# walktimizer.net
KiCad netlist of a schematic drawn in Altium Designer
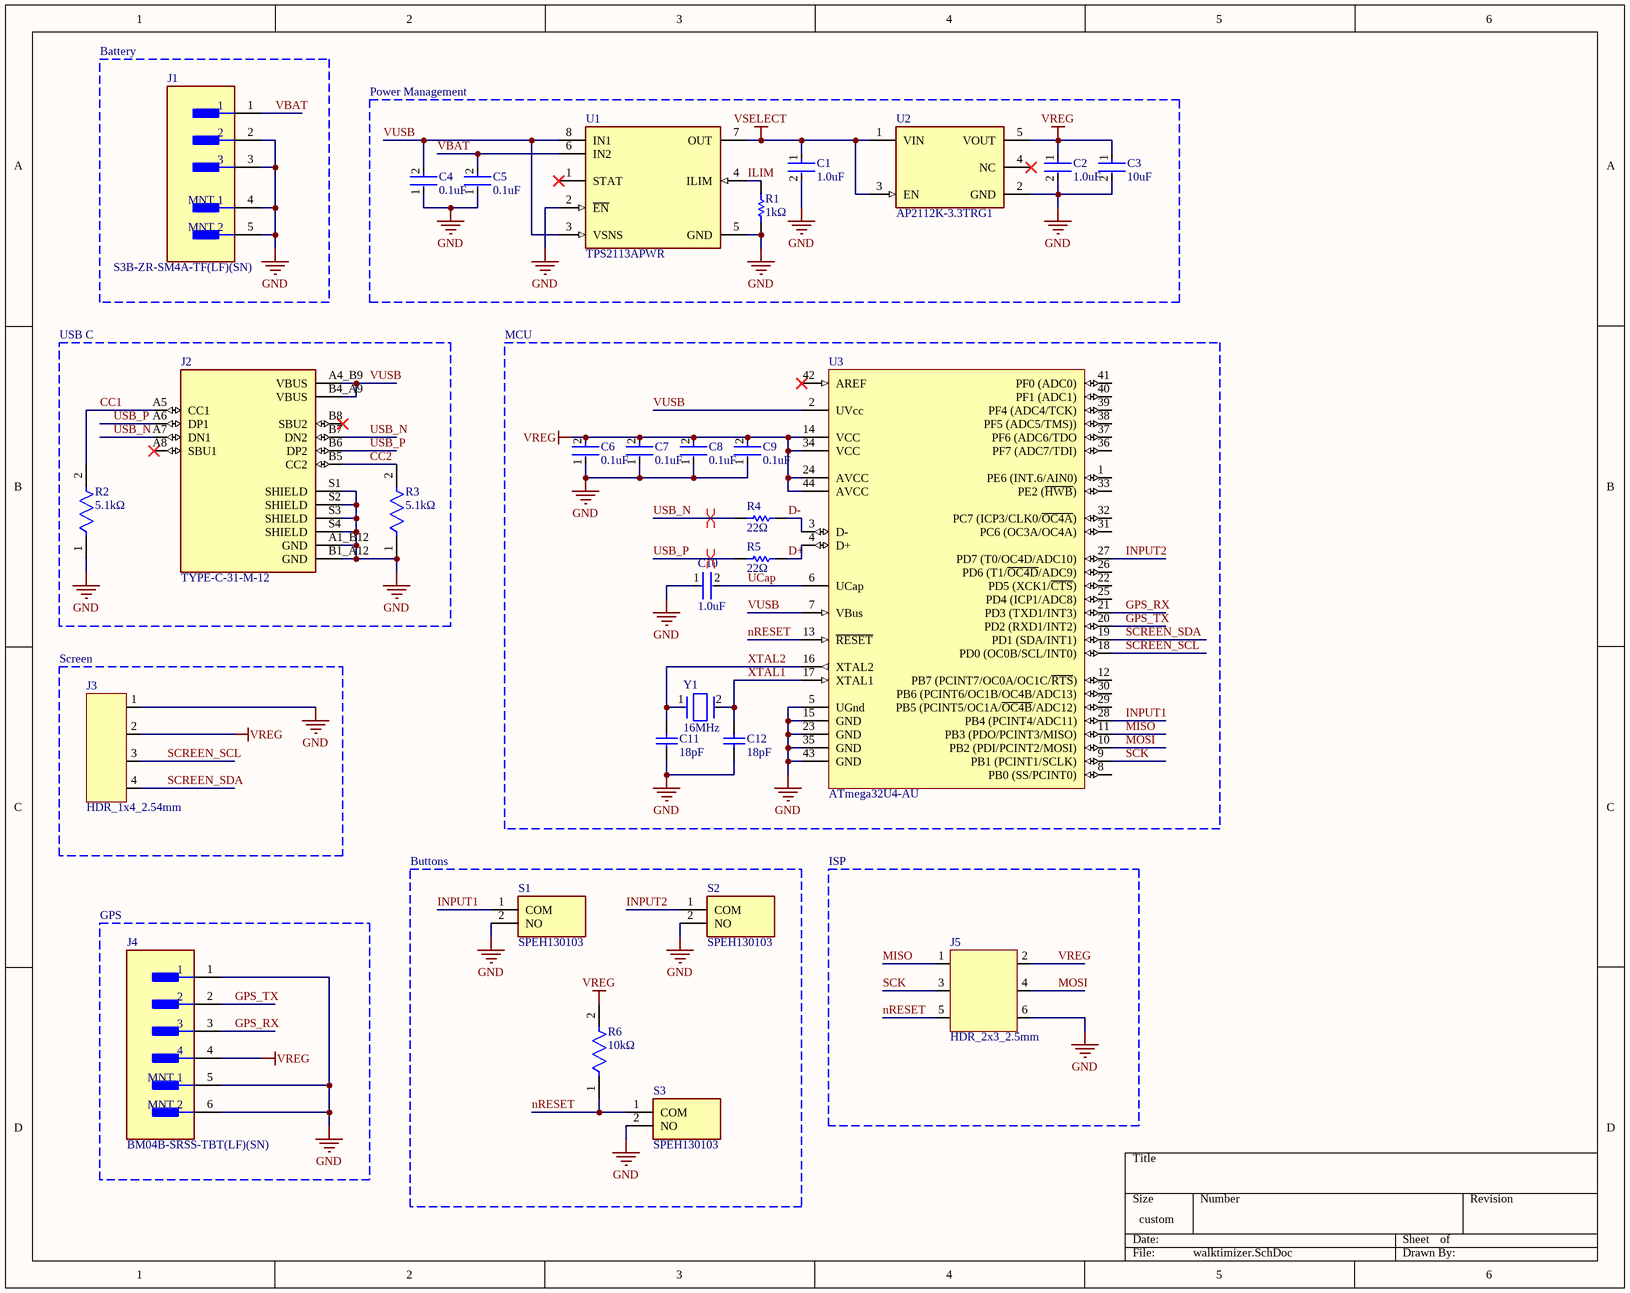
[diagram p0: walktimizer.SchDoc]

(export (version "E")
  (design (tool "Eeschema 10.0.6"))
  (components
    (comp (ref "C1")
      (value "1.0uF")
      (footprint "FP-GRT188-0_1-e0_2_0_5-IPC_B")
      (description "Multi-Layer Ceramic Capacitor 1uF 50V X5R ±10% 0603 Paper T/R\r\nGRT188R61H105KE13D")
      (fields (field (name "TOLERANCE") "10%"))
      (libsource (lib "Altium Content Vault") (part "02cd4be3c70576c341d710602a673aa"))
    )
    (comp (ref "C2")
      (value "1.0uF")
      (footprint "FP-GRT188-0_1-e0_2_0_5-IPC_B")
      (description "Multi-Layer Ceramic Capacitor 1uF 50V X5R ±10% 0603 Paper T/R\r\nGRT188R61H105KE13D")
      (fields (field (name "TOLERANCE") "10%"))
      (libsource (lib "Altium Content Vault") (part "02cd4be3c70576c341d710602a673aa"))
    )
    (comp (ref "C3")
      (value "10uF")
      (footprint "FP-GRM188-0_1-e0_2_0_55-IPC_A")
      (fields (field (name "VOLTAGE") "6.3V") (field (name "TOLERANCE") "20%"))
      (libsource (lib "Altium Content Vault") (part "02cd4be3c70576c341d710602a673aa"))
    )
    (comp (ref "C4")
      (value "0.1uF")
      (footprint "FP-GRM15-MFG")
      (description "CAP CER 0.1UF 16V X7R 0402\r\n\r\nGRM155R71C104KA88D")
      (fields (field (name "MANUFACTURER PART NUMBER") "GRM155R71C104KA88D") (field (name "TOLERANCE") "10%"))
      (libsource (lib "Altium Content Vault") (part "236180d848d6139a670b325ea6854c9"))
    )
    (comp (ref "C5")
      (value "0.1uF")
      (footprint "FP-GRM15-MFG")
      (description "CAP CER 0.1UF 16V X7R 0402\r\n\r\nGRM155R71C104KA88D")
      (fields (field (name "MANUFACTURER PART NUMBER") "GRM155R71C104KA88D") (field (name "TOLERANCE") "10%"))
      (libsource (lib "Altium Content Vault") (part "236180d848d6139a670b325ea6854c9"))
    )
    (comp (ref "C6")
      (value "0.1uF")
      (footprint "FP-GRM15-MFG")
      (description "CAP CER 0.1UF 16V X7R 0402\r\n\r\nGRM155R71C104KA88D")
      (fields (field (name "MANUFACTURER PART NUMBER") "GRM155R71C104KA88D") (field (name "TOLERANCE") "10%"))
      (libsource (lib "Altium Content Vault") (part "236180d848d6139a670b325ea6854c9"))
    )
    (comp (ref "C7")
      (value "0.1uF")
      (footprint "FP-GRM15-MFG")
      (description "CAP CER 0.1UF 16V X7R 0402\r\n\r\nGRM155R71C104KA88D")
      (fields (field (name "MANUFACTURER PART NUMBER") "GRM155R71C104KA88D") (field (name "TOLERANCE") "10%"))
      (libsource (lib "Altium Content Vault") (part "236180d848d6139a670b325ea6854c9"))
    )
    (comp (ref "C8")
      (value "0.1uF")
      (footprint "FP-GRM15-MFG")
      (description "CAP CER 0.1UF 16V X7R 0402\r\n\r\nGRM155R71C104KA88D")
      (fields (field (name "MANUFACTURER PART NUMBER") "GRM155R71C104KA88D") (field (name "TOLERANCE") "10%"))
      (libsource (lib "Altium Content Vault") (part "236180d848d6139a670b325ea6854c9"))
    )
    (comp (ref "C9")
      (value "0.1uF")
      (footprint "FP-GRM15-MFG")
      (description "CAP CER 0.1UF 16V X7R 0402\r\n\r\nGRM155R71C104KA88D")
      (fields (field (name "MANUFACTURER PART NUMBER") "GRM155R71C104KA88D") (field (name "TOLERANCE") "10%"))
      (libsource (lib "Altium Content Vault") (part "236180d848d6139a670b325ea6854c9"))
    )
    (comp (ref "C10")
      (value "1.0uF")
      (footprint "FP-GRT188-0_1-e0_2_0_5-IPC_B")
      (description "Multi-Layer Ceramic Capacitor 1uF 50V X5R ±10% 0603 Paper T/R\r\nGRT188R61H105KE13D")
      (fields (field (name "TOLERANCE") "10%"))
      (libsource (lib "Altium Content Vault") (part "02cd4be3c70576c341d710602a673aa"))
    )
    (comp (ref "C11")
      (value "18pF")
      (footprint "CAPC1608X90X40LL10T20")
      (fields (field (name "TOLERANCE") "1%"))
      (libsource (lib "Altium Content Vault") (part "CAP-NP-2"))
    )
    (comp (ref "C12")
      (value "18pF")
      (footprint "CAPC1608X90X40LL10T20")
      (fields (field (name "TOLERANCE") "1%"))
      (libsource (lib "Altium Content Vault") (part "CAP-NP-2"))
    )
    (comp (ref "J1")
      (value "S3B-ZR-SM4A-TF(LF)(SN)")
      (footprint "FP-S3B-ZR-SM4A-TF_LF_SN-MFG")
      (description "CONN HEADER SMD R/A 3POS 1.5MM")
      (libsource (lib "Altium Content Vault") (part "38689d6f3df0f9b234c6ddcef280d85"))
    )
    (comp (ref "J2")
      (value "TYPE-C-31-M-12")
      (footprint "HRO_TYPE-C-31-M-12")
      (description "USB Connectors 24 Receptacle 1 8.94*7.3mm RoHS")
      (fields (field (name "MF") "HRO Electronics Co., Ltd."))
      (libsource (lib "TYPE-C-31-M-12") (part "TYPE-C-31-M-12"))
    )
    (comp (ref "J3")
      (value "HDR_1x4_2.54mm")
      (footprint "HDR_1x4_2.5mm_TH")
      (description "2x3 2.54mm Pitch Header")
      (libsource (lib "symbolism") (part "HDR_1x4_2.54mm"))
    )
    (comp (ref "J4")
      (value "BM04B-SRSS-TBT(LF)(SN)")
      (footprint "FP-BM04B-SRSS-TBT_LF_SN-MFG")
      (description "CONN HEADER SMD 4POS 1MM")
      (libsource (lib "Altium Content Vault") (part "8e3688c4b118bffc0dd9b7401e414ba"))
    )
    (comp (ref "J5")
      (value "HDR_2x3_2.5mm")
      (footprint "HDR_2x3_2.5mm_TH")
      (description "2x3 2.54mm Pitch Header")
      (libsource (lib "symbolism") (part "HDR_2x3_2.5mm"))
    )
    (comp (ref "R1")
      (value "1kΩ")
      (footprint "RESC2013X60X35ML10T20")
      (fields (field (name "TOLERANCE") "1%") (field (name "MANUFACTURER") "Yageo"))
      (libsource (lib "Altium Content Vault") (part "RES-2"))
    )
    (comp (ref "R2")
      (value "5.1kΩ")
      (footprint "FP-CRCW0603-e3-IPC_C")
      (description "RES Thick Film, 5.1kΩ, 1%, 0.1W, 100ppm/°C, 0603\r\n\r\nCRCW06035K10FKEA")
      (fields (field (name "TOLERANCE") "1%"))
      (libsource (lib "Altium Content Vault") (part "1029c3af85768c4190bb7ad29bc67b5"))
    )
    (comp (ref "R3")
      (value "5.1kΩ")
      (footprint "FP-CRCW0603-e3-IPC_C")
      (description "RES Thick Film, 5.1kΩ, 1%, 0.1W, 100ppm/°C, 0603\r\n\r\nCRCW06035K10FKEA")
      (fields (field (name "TOLERANCE") "1%"))
      (libsource (lib "Altium Content Vault") (part "1029c3af85768c4190bb7ad29bc67b5"))
    )
    (comp (ref "R4")
      (value "22Ω")
      (footprint "RESC1005X40X25LL05T05")
      (description "CRCW040222R0FKED")
      (fields (field (name "MANUFACTURER") "Vishay Dale"))
      (libsource (lib "Altium Content Vault") (part "RES"))
    )
    (comp (ref "R5")
      (value "22Ω")
      (footprint "RESC1005X40X25LL05T05")
      (description "CRCW040222R0FKED")
      (fields (field (name "MANUFACTURER") "Vishay Dale"))
      (libsource (lib "Altium Content Vault") (part "RES"))
    )
    (comp (ref "R6")
      (value "10kΩ")
      (footprint "FP-RC0603-0_55-IPC_C")
      (description "RES 10K OHM 1% 1/10W 0603\r\nRC0603FR-0710KL")
      (fields (field (name "TOLERANCE") "1%"))
      (libsource (lib "Altium Content Vault") (part "1029c3af85768c4190bb7ad29bc67b5"))
    )
    (comp (ref "S1")
      (value "SPEH130103")
      (footprint "SamacSys:SPEH130103")
      (description "Switch")
      (fields (field (name "MOUSER PART NUMBER") "688-SPEH130101"))
      (libsource (lib "*") (part "SPEH130103"))
    )
    (comp (ref "S2")
      (value "SPEH130103")
      (footprint "SamacSys:SPEH130103")
      (description "Switch")
      (fields (field (name "MOUSER PART NUMBER") "688-SPEH130101"))
      (libsource (lib "*") (part "SPEH130103"))
    )
    (comp (ref "S3")
      (value "SPEH130103")
      (footprint "SamacSys:SPEH130103")
      (description "Switch")
      (fields (field (name "MOUSER PART NUMBER") "688-SPEH130101"))
      (libsource (lib "*") (part "SPEH130103"))
    )
    (comp (ref "U1")
      (value "TPS2113APWR")
      (footprint "FP-PW0008A-IPC_B")
      (description "IC OR CTRLR SRC SELECT 8TSSOP")
      (libsource (lib "Altium Content Vault") (part "883c2ec5d874d1801bc805f681b0625"))
    )
    (comp (ref "U2")
      (value "AP2112K-3.3TRG1")
      (footprint "FP-SOT25-IPC_A")
      (description "IC REG LINEAR 3.3V 600MA SOT25")
      (libsource (lib "Altium Content Vault") (part "c8ab751aee5229183125ab046a11caa"))
    )
    (comp (ref "U3")
      (value "ATmega32U4-AU")
      (footprint "44ML_M")
      (libsource (lib "Altium Content Vault") (part "MC-8B-ATM16U4-SQ44"))
    )
    (comp (ref "Y1")
      (value "16MHz")
      (footprint "FP-ABM3-MFG")
      (description "Crystal 16MHz ±20ppm 18pF SMD-2 5mm x 3.2mm\r\n\r\nABM3-16.000MHZ-D2Y-T")
      (fields (field (name "TOLERANCE") "20ppm"))
      (libsource (lib "Altium Content Vault") (part "c23a69dc6c9e2f18f2079038eb95dd1"))
    )
  )
  (nets
    (net (code "1") (name "/CC1") (class "Default")
      (node (ref "J2") (pin "A5") (pinfunction "CC1_A5") (pintype "bidirectional"))
      (node (ref "R2") (pin "2") (pinfunction "2_2") (pintype "passive"))
    )
    (net (code "2") (name "/CC2") (class "Default")
      (node (ref "J2") (pin "B5") (pinfunction "CC2_B5") (pintype "bidirectional"))
      (node (ref "R3") (pin "2") (pinfunction "2_2") (pintype "passive"))
    )
    (net (code "3") (name "/D+") (class "Default")
      (node (ref "R5") (pin "2") (pinfunction "2_2") (pintype "passive"))
      (node (ref "U3") (pin "4") (pinfunction "D+_4") (pintype "bidirectional"))
    )
    (net (code "4") (name "/D-") (class "Default")
      (node (ref "R4") (pin "2") (pinfunction "2_2") (pintype "passive"))
      (node (ref "U3") (pin "3") (pinfunction "D-_3") (pintype "bidirectional"))
    )
    (net (code "5") (name "/GPS_RX") (class "Default")
      (node (ref "J4") (pin "3") (pinfunction "3_3") (pintype "passive"))
      (node (ref "U3") (pin "21") (pinfunction "PD3_(TXD1/INT3)_21") (pintype "bidirectional"))
    )
    (net (code "6") (name "/GPS_TX") (class "Default")
      (node (ref "J4") (pin "2") (pinfunction "2_2") (pintype "passive"))
      (node (ref "U3") (pin "20") (pinfunction "PD2_(RXD1/INT2)_20") (pintype "bidirectional"))
    )
    (net (code "7") (name "/ILIM") (class "Default")
      (node (ref "R1") (pin "2") (pinfunction "2_2") (pintype "passive"))
      (node (ref "U1") (pin "4") (pinfunction "ILIM_4") (pintype "input"))
    )
    (net (code "8") (name "/INPUT1") (class "Default")
      (node (ref "S1") (pin "1") (pinfunction "COM_1") (pintype "passive"))
      (node (ref "U3") (pin "28") (pinfunction "PB4_(PCINT4/ADC11)_28") (pintype "bidirectional"))
    )
    (net (code "9") (name "/INPUT2") (class "Default")
      (node (ref "S2") (pin "1") (pinfunction "COM_1") (pintype "passive"))
      (node (ref "U3") (pin "27") (pinfunction "PD7_(T0/OC4D/ADC10)_27") (pintype "bidirectional"))
    )
    (net (code "10") (name "/MISO") (class "Default")
      (node (ref "J5") (pin "1") (pintype "passive"))
      (node (ref "U3") (pin "11") (pinfunction "PB3_(PDO/PCINT3/MISO)_11") (pintype "bidirectional"))
    )
    (net (code "11") (name "/MOSI") (class "Default")
      (node (ref "J5") (pin "4") (pintype "passive"))
      (node (ref "U3") (pin "10") (pinfunction "PB2_(PDI/PCINT2/MOSI)_10") (pintype "bidirectional"))
    )
    (net (code "12") (name "/SCK") (class "Default")
      (node (ref "J5") (pin "3") (pintype "passive"))
      (node (ref "U3") (pin "9") (pinfunction "PB1_(PCINT1/SCLK)_9") (pintype "bidirectional"))
    )
    (net (code "13") (name "/SCREEN_SCL") (class "Default")
      (node (ref "J3") (pin "3") (pintype "passive"))
      (node (ref "U3") (pin "18") (pinfunction "PD0_(OC0B/SCL/INT0)_18") (pintype "bidirectional"))
    )
    (net (code "14") (name "/SCREEN_SDA") (class "Default")
      (node (ref "J3") (pin "4") (pintype "passive"))
      (node (ref "U3") (pin "19") (pinfunction "PD1_(SDA/INT1)_19") (pintype "bidirectional"))
    )
    (net (code "15") (name "/UCap") (class "Default")
      (node (ref "C10") (pin "2") (pinfunction "2_2") (pintype "passive"))
      (node (ref "U3") (pin "6") (pinfunction "UCap_6") (pintype "passive"))
    )
    (net (code "16") (name "/USB_N") (class "Default")
      (node (ref "J2") (pin "A7") (pinfunction "DN1_A7") (pintype "bidirectional"))
      (node (ref "J2") (pin "B7") (pinfunction "DN2_B7") (pintype "bidirectional"))
      (node (ref "R4") (pin "1") (pinfunction "1_1") (pintype "passive"))
    )
    (net (code "17") (name "/USB_P") (class "Default")
      (node (ref "J2") (pin "A6") (pinfunction "DP1_A6") (pintype "bidirectional"))
      (node (ref "J2") (pin "B6") (pinfunction "DP2_B6") (pintype "bidirectional"))
      (node (ref "R5") (pin "1") (pinfunction "1_1") (pintype "passive"))
    )
    (net (code "18") (name "/VBAT") (class "Default")
      (node (ref "C5") (pin "2") (pinfunction "2_2") (pintype "passive"))
      (node (ref "J1") (pin "1") (pinfunction "1_1") (pintype "passive"))
      (node (ref "U1") (pin "6") (pinfunction "IN2_6") (pintype "power_in"))
    )
    (net (code "19") (name "/VUSB") (class "Default")
      (node (ref "C4") (pin "2") (pinfunction "2_2") (pintype "passive"))
      (node (ref "J2") (pin "A4_B9") (pinfunction "VBUS_A4_B9") (pintype "power_in"))
      (node (ref "J2") (pin "B4_A9") (pinfunction "VBUS_B4_A9") (pintype "power_in"))
      (node (ref "U1") (pin "3") (pinfunction "VSNS_3") (pintype "input"))
      (node (ref "U1") (pin "8") (pinfunction "IN1_8") (pintype "power_in"))
      (node (ref "U3") (pin "2") (pinfunction "UVcc_2") (pintype "power_in"))
      (node (ref "U3") (pin "7") (pinfunction "VBus_7") (pintype "input"))
    )
    (net (code "20") (name "/XTAL1") (class "Default")
      (node (ref "C12") (pin "2") (pinfunction "2_2") (pintype "passive"))
      (node (ref "U3") (pin "17") (pinfunction "XTAL1_17") (pintype "input"))
      (node (ref "Y1") (pin "2") (pinfunction "2_2") (pintype "passive"))
    )
    (net (code "21") (name "/XTAL2") (class "Default")
      (node (ref "C11") (pin "2") (pinfunction "2_2") (pintype "passive"))
      (node (ref "U3") (pin "16") (pinfunction "XTAL2_16") (pintype "output"))
      (node (ref "Y1") (pin "1") (pinfunction "1_1") (pintype "passive"))
    )
    (net (code "22") (name "/nRESET") (class "Default")
      (node (ref "J5") (pin "5") (pintype "passive"))
      (node (ref "R6") (pin "1") (pinfunction "1_1") (pintype "passive"))
      (node (ref "S3") (pin "1") (pinfunction "COM_1") (pintype "passive"))
      (node (ref "U3") (pin "13") (pinfunction "~{RESET}_13") (pintype "input"))
    )
    (net (code "23") (name "GND") (class "Default")
      (node (ref "C1") (pin "2") (pinfunction "2_2") (pintype "passive"))
      (node (ref "C10") (pin "1") (pinfunction "1_1") (pintype "passive"))
      (node (ref "C11") (pin "1") (pinfunction "1_1") (pintype "passive"))
      (node (ref "C12") (pin "1") (pinfunction "1_1") (pintype "passive"))
      (node (ref "C2") (pin "2") (pinfunction "2_2") (pintype "passive"))
      (node (ref "C3") (pin "2") (pinfunction "2_2") (pintype "passive"))
      (node (ref "C4") (pin "1") (pinfunction "1_1") (pintype "passive"))
      (node (ref "C5") (pin "1") (pinfunction "1_1") (pintype "passive"))
      (node (ref "C6") (pin "1") (pinfunction "1_1") (pintype "passive"))
      (node (ref "C7") (pin "1") (pinfunction "1_1") (pintype "passive"))
      (node (ref "C8") (pin "1") (pinfunction "1_1") (pintype "passive"))
      (node (ref "C9") (pin "1") (pinfunction "1_1") (pintype "passive"))
      (node (ref "J1") (pin "2") (pinfunction "2_2") (pintype "passive"))
      (node (ref "J1") (pin "3") (pinfunction "3_3") (pintype "passive"))
      (node (ref "J1") (pin "4") (pinfunction "MNT_1_4") (pintype "passive"))
      (node (ref "J1") (pin "5") (pinfunction "MNT_2_5") (pintype "passive"))
      (node (ref "J2") (pin "A1_B12") (pinfunction "GND_A1_B12") (pintype "power_in"))
      (node (ref "J2") (pin "B1_A12") (pinfunction "GND_B1_A12") (pintype "power_in"))
      (node (ref "J2") (pin "S1") (pinfunction "SHIELD_S1") (pintype "passive"))
      (node (ref "J2") (pin "S2") (pinfunction "SHIELD_S2") (pintype "passive"))
      (node (ref "J2") (pin "S3") (pinfunction "SHIELD_S3") (pintype "passive"))
      (node (ref "J2") (pin "S4") (pinfunction "SHIELD_S4") (pintype "passive"))
      (node (ref "J3") (pin "1") (pintype "passive"))
      (node (ref "J4") (pin "1") (pinfunction "1_1") (pintype "passive"))
      (node (ref "J4") (pin "5") (pinfunction "MNT_1_5") (pintype "passive"))
      (node (ref "J4") (pin "6") (pinfunction "MNT_2_6") (pintype "passive"))
      (node (ref "J5") (pin "6") (pintype "passive"))
      (node (ref "R1") (pin "1") (pinfunction "1_1") (pintype "passive"))
      (node (ref "R2") (pin "1") (pinfunction "1_1") (pintype "passive"))
      (node (ref "R3") (pin "1") (pinfunction "1_1") (pintype "passive"))
      (node (ref "S1") (pin "2") (pinfunction "NO_2") (pintype "passive"))
      (node (ref "S2") (pin "2") (pinfunction "NO_2") (pintype "passive"))
      (node (ref "S3") (pin "2") (pinfunction "NO_2") (pintype "passive"))
      (node (ref "U1") (pin "2") (pinfunction "~{EN}_2") (pintype "input"))
      (node (ref "U1") (pin "5") (pinfunction "GND_5") (pintype "power_in"))
      (node (ref "U2") (pin "2") (pinfunction "GND_2") (pintype "power_in"))
      (node (ref "U3") (pin "15") (pinfunction "GND_15") (pintype "power_in"))
      (node (ref "U3") (pin "23") (pinfunction "GND_23") (pintype "power_in"))
      (node (ref "U3") (pin "35") (pinfunction "GND_35") (pintype "power_in"))
      (node (ref "U3") (pin "43") (pinfunction "GND_43") (pintype "power_in"))
      (node (ref "U3") (pin "5") (pinfunction "UGnd_5") (pintype "power_in"))
    )
    (net (code "24") (name "VREG") (class "Default")
      (node (ref "C2") (pin "1") (pinfunction "1_1") (pintype "passive"))
      (node (ref "C3") (pin "1") (pinfunction "1_1") (pintype "passive"))
      (node (ref "C6") (pin "2") (pinfunction "2_2") (pintype "passive"))
      (node (ref "C7") (pin "2") (pinfunction "2_2") (pintype "passive"))
      (node (ref "C8") (pin "2") (pinfunction "2_2") (pintype "passive"))
      (node (ref "C9") (pin "2") (pinfunction "2_2") (pintype "passive"))
      (node (ref "J3") (pin "2") (pintype "passive"))
      (node (ref "J4") (pin "4") (pinfunction "4_4") (pintype "passive"))
      (node (ref "J5") (pin "2") (pintype "passive"))
      (node (ref "R6") (pin "2") (pinfunction "2_2") (pintype "passive"))
      (node (ref "U2") (pin "5") (pinfunction "VOUT_5") (pintype "power_in"))
      (node (ref "U3") (pin "14") (pinfunction "VCC_14") (pintype "power_in"))
      (node (ref "U3") (pin "24") (pinfunction "AVCC_24") (pintype "power_in"))
      (node (ref "U3") (pin "34") (pinfunction "VCC_34") (pintype "power_in"))
      (node (ref "U3") (pin "44") (pinfunction "AVCC_44") (pintype "power_in"))
    )
    (net (code "25") (name "VSELECT") (class "Default")
      (node (ref "C1") (pin "1") (pinfunction "1_1") (pintype "passive"))
      (node (ref "U1") (pin "7") (pinfunction "OUT_7") (pintype "power_in"))
      (node (ref "U2") (pin "1") (pinfunction "VIN_1") (pintype "power_in"))
      (node (ref "U2") (pin "3") (pinfunction "EN_3") (pintype "input"))
    )
    (net (code "26") (name "unconnected-(J2-SBU1-PadA8)") (class "Default")
      (node (ref "J2") (pin "A8") (pinfunction "SBU1_A8") (pintype "bidirectional+no_connect"))
    )
    (net (code "27") (name "unconnected-(J2-SBU2-PadB8)") (class "Default")
      (node (ref "J2") (pin "B8") (pinfunction "SBU2_B8") (pintype "bidirectional+no_connect"))
    )
    (net (code "28") (name "unconnected-(U1-STAT-Pad1)") (class "Default")
      (node (ref "U1") (pin "1") (pinfunction "STAT_1") (pintype "tri_state+no_connect"))
    )
    (net (code "29") (name "unconnected-(U2-NC-Pad4)") (class "Default")
      (node (ref "U2") (pin "4") (pinfunction "NC_4") (pintype "passive+no_connect"))
    )
    (net (code "30") (name "unconnected-(U3-AREF-Pad42)") (class "Default")
      (node (ref "U3") (pin "42") (pinfunction "AREF_42") (pintype "input+no_connect"))
    )
    (net (code "31") (name "unconnected-(U3-PB0_(SS{slash}PCINT0)-Pad8)") (class "Default")
      (node (ref "U3") (pin "8") (pinfunction "PB0_(SS/PCINT0)_8") (pintype "bidirectional"))
    )
    (net (code "32") (name "unconnected-(U3-PB5_(PCINT5{slash}OC1A{slash}~{OC4B}{slash}ADC12)-Pad29)") (class "Default")
      (node (ref "U3") (pin "29") (pinfunction "PB5_(PCINT5/OC1A/~{OC4B}/ADC12)_29") (pintype "bidirectional"))
    )
    (net (code "33") (name "unconnected-(U3-PB6_(PCINT6{slash}OC1B{slash}OC4B{slash}ADC13)-Pad30)") (class "Default")
      (node (ref "U3") (pin "30") (pinfunction "PB6_(PCINT6/OC1B/OC4B/ADC13)_30") (pintype "bidirectional"))
    )
    (net (code "34") (name "unconnected-(U3-PB7_(PCINT7{slash}OC0A{slash}OC1C{slash}~{RTS})-Pad12)") (class "Default")
      (node (ref "U3") (pin "12") (pinfunction "PB7_(PCINT7/OC0A/OC1C/~{RTS})_12") (pintype "bidirectional"))
    )
    (net (code "35") (name "unconnected-(U3-PC6_(OC3A{slash}OC4A)-Pad31)") (class "Default")
      (node (ref "U3") (pin "31") (pinfunction "PC6_(OC3A/OC4A)_31") (pintype "bidirectional"))
    )
    (net (code "36") (name "unconnected-(U3-PC7_(ICP3{slash}CLK0{slash}~{OC4A})-Pad32)") (class "Default")
      (node (ref "U3") (pin "32") (pinfunction "PC7_(ICP3/CLK0/~{OC4A})_32") (pintype "bidirectional"))
    )
    (net (code "37") (name "unconnected-(U3-PD4_(ICP1{slash}ADC8)-Pad25)") (class "Default")
      (node (ref "U3") (pin "25") (pinfunction "PD4_(ICP1/ADC8)_25") (pintype "bidirectional"))
    )
    (net (code "38") (name "unconnected-(U3-PD5_(XCK1{slash}~{CTS})-Pad22)") (class "Default")
      (node (ref "U3") (pin "22") (pinfunction "PD5_(XCK1/~{CTS})_22") (pintype "bidirectional"))
    )
    (net (code "39") (name "unconnected-(U3-PD6_(T1{slash}~{OC4D}{slash}ADC9)-Pad26)") (class "Default")
      (node (ref "U3") (pin "26") (pinfunction "PD6_(T1/~{OC4D}/ADC9)_26") (pintype "bidirectional"))
    )
    (net (code "40") (name "unconnected-(U3-PE2_(~{HWB})-Pad33)") (class "Default")
      (node (ref "U3") (pin "33") (pinfunction "PE2_(~{HWB})_33") (pintype "bidirectional"))
    )
    (net (code "41") (name "unconnected-(U3-PE6_(INT.6{slash}AIN0)-Pad1)") (class "Default")
      (node (ref "U3") (pin "1") (pinfunction "PE6_(INT.6/AIN0)_1") (pintype "bidirectional"))
    )
    (net (code "42") (name "unconnected-(U3-PF0_(ADC0)-Pad41)") (class "Default")
      (node (ref "U3") (pin "41") (pinfunction "PF0_(ADC0)_41") (pintype "bidirectional"))
    )
    (net (code "43") (name "unconnected-(U3-PF1_(ADC1)-Pad40)") (class "Default")
      (node (ref "U3") (pin "40") (pinfunction "PF1_(ADC1)_40") (pintype "bidirectional"))
    )
    (net (code "44") (name "unconnected-(U3-PF4_(ADC4{slash}TCK)-Pad39)") (class "Default")
      (node (ref "U3") (pin "39") (pinfunction "PF4_(ADC4/TCK)_39") (pintype "bidirectional"))
    )
    (net (code "45") (name "unconnected-(U3-PF5_(ADC5{slash}TMS))-Pad38)") (class "Default")
      (node (ref "U3") (pin "38") (pinfunction "PF5_(ADC5/TMS))_38") (pintype "bidirectional"))
    )
    (net (code "46") (name "unconnected-(U3-PF6_(ADC6{slash}TDO-Pad37)") (class "Default")
      (node (ref "U3") (pin "37") (pinfunction "PF6_(ADC6/TDO_37") (pintype "bidirectional"))
    )
    (net (code "47") (name "unconnected-(U3-PF7_(ADC7{slash}TDI)-Pad36)") (class "Default")
      (node (ref "U3") (pin "36") (pinfunction "PF7_(ADC7/TDI)_36") (pintype "bidirectional"))
    )
  )
)
